# PicoDucky.net
KiCad netlist of a schematic drawn in EasyEDA Pro
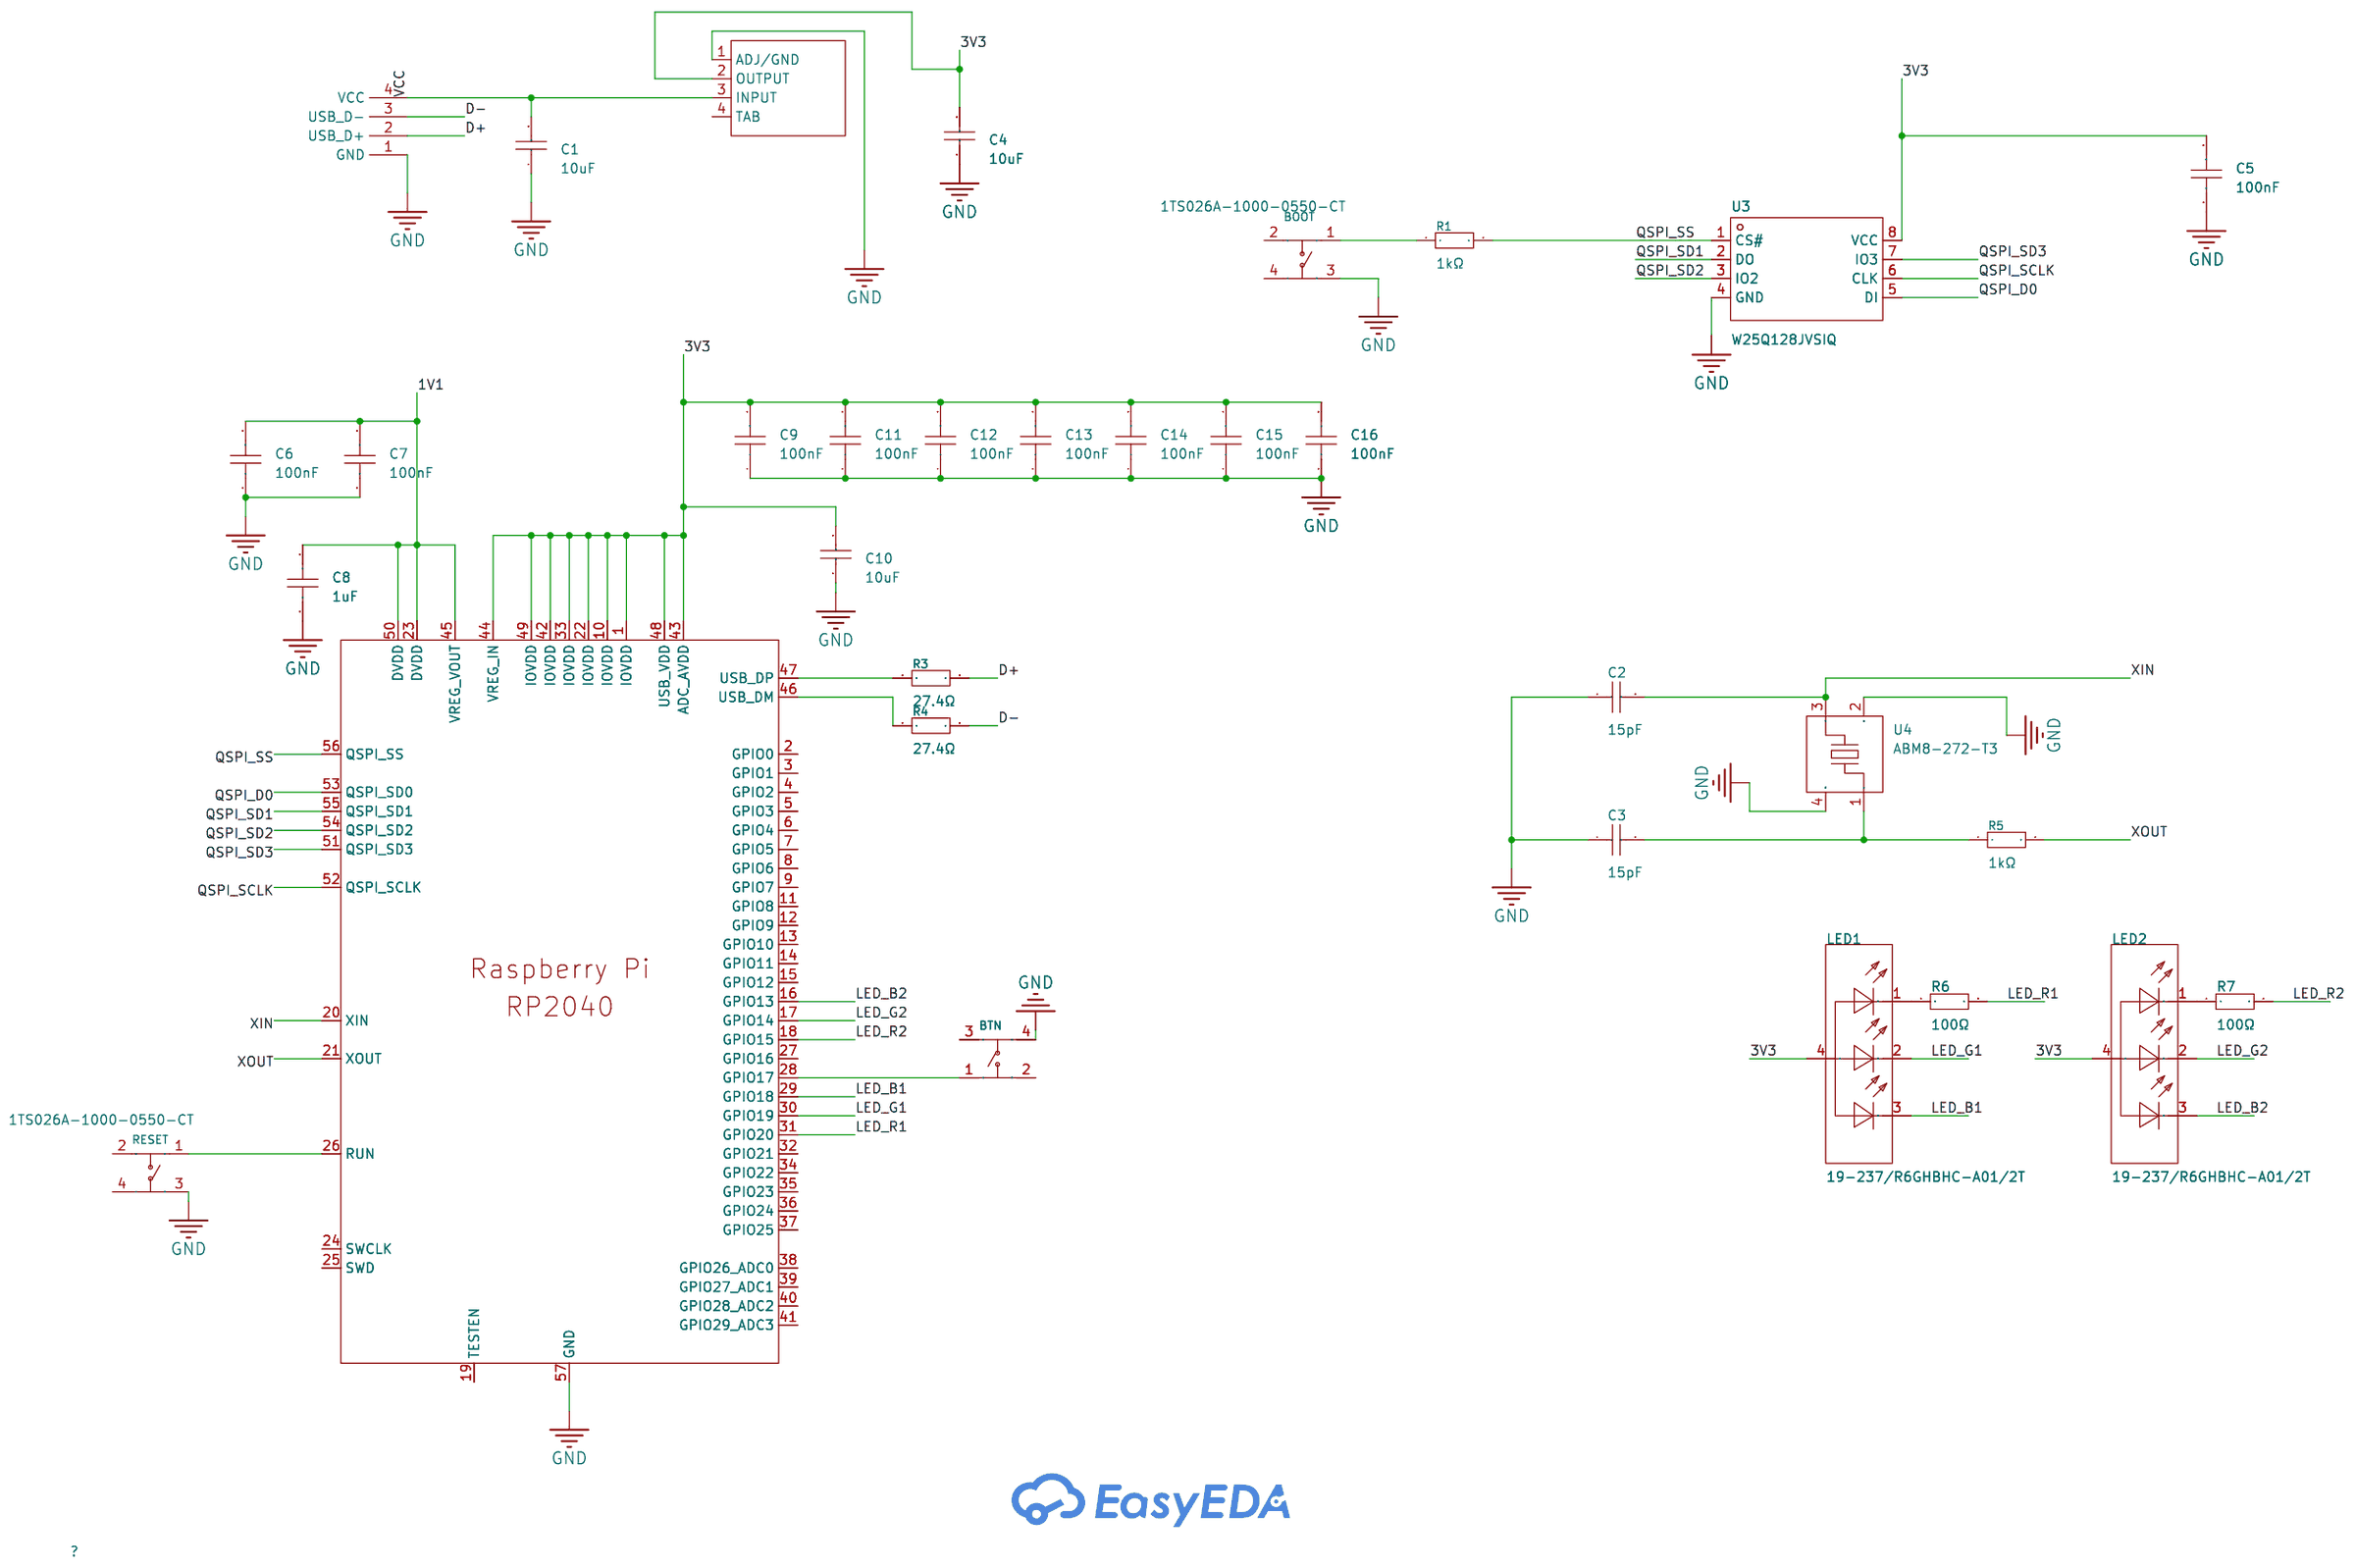
[diagram p0: schematic sheet]

(export (version "E")
  (design (tool "Eeschema 10.0.6"))
  (components
    (comp (ref "BOOT")
      (value "1TS026A-1000-0550-CT")
      (footprint "easyedapro:SW-SMD_4P-L2.6-W1.6-P0.75-LS3.0")
      (fields (field (name "Manufacturer") "HYP(鸿源精密)"))
      (libsource (lib "easyedapro") (part "1TS026A-1000-0550-CT"))
    )
    (comp (ref "BTN")
      (value "1TS026A-1000-0550-CT")
      (footprint "easyedapro:SW-SMD_4P-L2.6-W1.6-P0.75-LS3.0")
      (fields (field (name "Manufacturer") "HYP(鸿源精密)"))
      (libsource (lib "easyedapro") (part "1TS026A-1000-0550-CT"))
    )
    (comp (ref "C1")
      (value "10uF")
      (footprint "easyedapro:C0402")
      (fields
        (field (name "Manufacturer Part") "CL05A106MQ5NUNC")
        (field (name "Manufacturer") "SAMSUNG(三星)")
      )
      (libsource (lib "easyedapro") (part "CL05A106MQ5NUNC"))
    )
    (comp (ref "C2")
      (value "15pF")
      (footprint "easyedapro:C0402")
      (fields (field (name "Manufacturer Part") "0402CG150J500NT") (field (name "Manufacturer") "FH(风华)"))
      (libsource (lib "easyedapro") (part "0402CG150J500NT"))
    )
    (comp (ref "C3")
      (value "15pF")
      (footprint "easyedapro:C0402")
      (fields (field (name "Manufacturer Part") "0402CG150J500NT") (field (name "Manufacturer") "FH(风华)"))
      (libsource (lib "easyedapro") (part "0402CG150J500NT"))
    )
    (comp (ref "C4")
      (value "10uF")
      (footprint "easyedapro:C0402")
      (fields
        (field (name "Manufacturer Part") "CL05A106MQ5NUNC")
        (field (name "Manufacturer") "SAMSUNG(三星)")
      )
      (libsource (lib "easyedapro") (part "CL05A106MQ5NUNC"))
    )
    (comp (ref "C5")
      (value "100nF")
      (footprint "easyedapro:C0402")
      (fields
        (field (name "Manufacturer Part") "CL05B104KO5NNNC")
        (field (name "Manufacturer") "SAMSUNG(三星)")
      )
      (libsource (lib "easyedapro") (part "CL05B104KO5NNNC"))
    )
    (comp (ref "C6")
      (value "100nF")
      (footprint "easyedapro:C0402")
      (fields
        (field (name "Manufacturer Part") "CL05B104KO5NNNC")
        (field (name "Manufacturer") "SAMSUNG(三星)")
      )
      (libsource (lib "easyedapro") (part "CL05B104KO5NNNC"))
    )
    (comp (ref "C7")
      (value "100nF")
      (footprint "easyedapro:C0402")
      (fields
        (field (name "Manufacturer Part") "CL05B104KO5NNNC")
        (field (name "Manufacturer") "SAMSUNG(三星)")
      )
      (libsource (lib "easyedapro") (part "CL05B104KO5NNNC"))
    )
    (comp (ref "C8")
      (value "1uF")
      (footprint "easyedapro:C0402")
      (fields
        (field (name "Manufacturer Part") "CL05A105KA5NQNC")
        (field (name "Manufacturer") "SAMSUNG(三星)")
      )
      (libsource (lib "easyedapro") (part "CL05A105KA5NQNC"))
    )
    (comp (ref "C9")
      (value "100nF")
      (footprint "easyedapro:C0402")
      (fields
        (field (name "Manufacturer Part") "CL05B104KO5NNNC")
        (field (name "Manufacturer") "SAMSUNG(三星)")
      )
      (libsource (lib "easyedapro") (part "CL05B104KO5NNNC"))
    )
    (comp (ref "C10")
      (value "10uF")
      (footprint "easyedapro:C0402")
      (fields
        (field (name "Manufacturer Part") "CL05A106MQ5NUNC")
        (field (name "Manufacturer") "SAMSUNG(三星)")
      )
      (libsource (lib "easyedapro") (part "CL05A106MQ5NUNC"))
    )
    (comp (ref "C11")
      (value "100nF")
      (footprint "easyedapro:C0402")
      (fields
        (field (name "Manufacturer Part") "CL05B104KO5NNNC")
        (field (name "Manufacturer") "SAMSUNG(三星)")
      )
      (libsource (lib "easyedapro") (part "CL05B104KO5NNNC"))
    )
    (comp (ref "C12")
      (value "100nF")
      (footprint "easyedapro:C0402")
      (fields
        (field (name "Manufacturer Part") "CL05B104KO5NNNC")
        (field (name "Manufacturer") "SAMSUNG(三星)")
      )
      (libsource (lib "easyedapro") (part "CL05B104KO5NNNC"))
    )
    (comp (ref "C13")
      (value "100nF")
      (footprint "easyedapro:C0402")
      (fields
        (field (name "Manufacturer Part") "CL05B104KO5NNNC")
        (field (name "Manufacturer") "SAMSUNG(三星)")
      )
      (libsource (lib "easyedapro") (part "CL05B104KO5NNNC"))
    )
    (comp (ref "C14")
      (value "100nF")
      (footprint "easyedapro:C0402")
      (fields
        (field (name "Manufacturer Part") "CL05B104KO5NNNC")
        (field (name "Manufacturer") "SAMSUNG(三星)")
      )
      (libsource (lib "easyedapro") (part "CL05B104KO5NNNC"))
    )
    (comp (ref "C15")
      (value "100nF")
      (footprint "easyedapro:C0402")
      (fields
        (field (name "Manufacturer Part") "CL05B104KO5NNNC")
        (field (name "Manufacturer") "SAMSUNG(三星)")
      )
      (libsource (lib "easyedapro") (part "CL05B104KO5NNNC"))
    )
    (comp (ref "C16")
      (value "100nF")
      (footprint "easyedapro:C0402")
      (fields
        (field (name "Manufacturer Part") "CL05B104KO5NNNC")
        (field (name "Manufacturer") "SAMSUNG(三星)")
      )
      (libsource (lib "easyedapro") (part "CL05B104KO5NNNC"))
    )
    (comp (ref "LED1")
      (value "19-237/R6GHBHC-A01/2T")
      (footprint "easyedapro:LED-ARRAY-SMD_4P-L1.6-W1.6-BL-CW")
      (fields (field (name "Manufacturer") "EVERLIGHT(亿光)"))
      (libsource (lib "easyedapro") (part "19-237/R6GHBHC-A01/2T"))
    )
    (comp (ref "LED2")
      (value "19-237/R6GHBHC-A01/2T")
      (footprint "easyedapro:LED-ARRAY-SMD_4P-L1.6-W1.6-BL-CW")
      (fields (field (name "Manufacturer") "EVERLIGHT(亿光)"))
      (libsource (lib "easyedapro") (part "19-237/R6GHBHC-A01/2T"))
    )
    (comp (ref "R1")
      (value "1kΩ")
      (footprint "easyedapro:R0402")
      (fields
        (field (name "Manufacturer Part") "0402WGF1001TCE")
        (field (name "Manufacturer") "UNI-ROYAL(厚声)")
      )
      (libsource (lib "easyedapro") (part "0402WGF1001TCE"))
    )
    (comp (ref "R3")
      (value "27.4Ω")
      (footprint "easyedapro:R0402")
      (fields
        (field (name "Manufacturer Part") "0402WGF274JTCE")
        (field (name "Manufacturer") "UNI-ROYAL(厚声)")
      )
      (libsource (lib "easyedapro") (part "0402WGF274JTCE"))
    )
    (comp (ref "R4")
      (value "27.4Ω")
      (footprint "easyedapro:R0402")
      (fields
        (field (name "Manufacturer Part") "0402WGF274JTCE")
        (field (name "Manufacturer") "UNI-ROYAL(厚声)")
      )
      (libsource (lib "easyedapro") (part "0402WGF274JTCE"))
    )
    (comp (ref "R5")
      (value "1kΩ")
      (footprint "easyedapro:R0402")
      (fields
        (field (name "Manufacturer Part") "0402WGF1001TCE")
        (field (name "Manufacturer") "UNI-ROYAL(厚声)")
      )
      (libsource (lib "easyedapro") (part "0402WGF1001TCE"))
    )
    (comp (ref "R6")
      (value "100Ω")
      (footprint "easyedapro:R0402")
      (fields
        (field (name "Manufacturer Part") "0402WGF1000TCE")
        (field (name "Manufacturer") "UNI-ROYAL(厚声)")
      )
      (libsource (lib "easyedapro") (part "0402WGF1000TCE"))
    )
    (comp (ref "R7")
      (value "100Ω")
      (footprint "easyedapro:R0402")
      (fields
        (field (name "Manufacturer Part") "0402WGF1000TCE")
        (field (name "Manufacturer") "UNI-ROYAL(厚声)")
      )
      (libsource (lib "easyedapro") (part "0402WGF1000TCE"))
    )
    (comp (ref "RESET")
      (value "1TS026A-1000-0550-CT")
      (footprint "easyedapro:SW-SMD_4P-L2.6-W1.6-P0.75-LS3.0")
      (fields (field (name "Manufacturer") "HYP(鸿源精密)"))
      (libsource (lib "easyedapro") (part "1TS026A-1000-0550-CT"))
    )
    (comp (ref "U1")
      (value "RP2040")
      (footprint "easyedapro:QFN-56_L7.0-W7.0-P0.40-TL-EP4.0")
      (fields (field (name "Manufacturer") "Raspberry Pi(树莓派)"))
      (libsource (lib "easyedapro") (part "RP2040_C2961140"))
    )
    (comp (ref "U2")
      (value "NCP1117ST33T3G")
      (footprint "easyedapro:SOT-223-3_L6.5-W3.4-P2.30-LS7.0-BR")
      (fields (field (name "Manufacturer") "onsemi(安森美)"))
      (libsource (lib "easyedapro") (part "NCP1117ST33T3G"))
    )
    (comp (ref "U3")
      (value "W25Q128JVSIQ")
      (footprint "easyedapro:SOIC-8_L5.3-W5.3-P1.27-LS8.0-BL")
      (fields (field (name "Manufacturer") "WINBOND(华邦)"))
      (libsource (lib "easyedapro") (part "W25Q128JVSIQTR"))
    )
    (comp (ref "U4")
      (value "ABM8-272-T3")
      (footprint "easyedapro:CRYSTAL-SMD_4P-L3.2-W2.5-BL")
      (fields (field (name "Manufacturer") "ABRACON"))
      (libsource (lib "easyedapro") (part "ABM8-272-T3_C20625731"))
    )
    (comp (ref "X1")
      (value "~")
      (footprint "easyedapro:USBA_PCB")
      (description "USB-A PCB")
      (libsource (lib "easyedapro") (part "USBA_PCB"))
    )
  )
  (nets
    (net (code "1") (name "/1V1") (class "Default")
      (node (ref "C6") (pin "2") (pinfunction "2_2") (pintype "unspecified"))
      (node (ref "C7") (pin "2") (pinfunction "2_2") (pintype "unspecified"))
      (node (ref "C8") (pin "2") (pinfunction "2_2") (pintype "unspecified"))
      (node (ref "U1") (pin "23") (pinfunction "DVDD_23") (pintype "bidirectional"))
      (node (ref "U1") (pin "45") (pinfunction "VREG_VOUT_45") (pintype "bidirectional"))
      (node (ref "U1") (pin "50") (pinfunction "DVDD_50") (pintype "bidirectional"))
    )
    (net (code "2") (name "/3V3") (class "Default")
      (node (ref "C10") (pin "2") (pinfunction "2_2") (pintype "input"))
      (node (ref "C11") (pin "2") (pinfunction "2_2") (pintype "unspecified"))
      (node (ref "C12") (pin "2") (pinfunction "2_2") (pintype "unspecified"))
      (node (ref "C13") (pin "2") (pinfunction "2_2") (pintype "unspecified"))
      (node (ref "C14") (pin "2") (pinfunction "2_2") (pintype "unspecified"))
      (node (ref "C15") (pin "2") (pinfunction "2_2") (pintype "unspecified"))
      (node (ref "C16") (pin "2") (pinfunction "2_2") (pintype "unspecified"))
      (node (ref "C4") (pin "2") (pinfunction "2_2") (pintype "input"))
      (node (ref "C5") (pin "2") (pinfunction "2_2") (pintype "unspecified"))
      (node (ref "C9") (pin "2") (pinfunction "2_2") (pintype "unspecified"))
      (node (ref "LED1") (pin "4") (pinfunction "+_4") (pintype "unspecified"))
      (node (ref "LED2") (pin "4") (pinfunction "+_4") (pintype "unspecified"))
      (node (ref "U1") (pin "1") (pinfunction "IOVDD_1") (pintype "bidirectional"))
      (node (ref "U1") (pin "10") (pinfunction "IOVDD_10") (pintype "bidirectional"))
      (node (ref "U1") (pin "22") (pinfunction "IOVDD_22") (pintype "bidirectional"))
      (node (ref "U1") (pin "33") (pinfunction "IOVDD_33") (pintype "bidirectional"))
      (node (ref "U1") (pin "42") (pinfunction "IOVDD_42") (pintype "bidirectional"))
      (node (ref "U1") (pin "43") (pinfunction "ADC_AVDD_43") (pintype "bidirectional"))
      (node (ref "U1") (pin "44") (pinfunction "VREG_IN_44") (pintype "bidirectional"))
      (node (ref "U1") (pin "48") (pinfunction "USB_VDD_48") (pintype "bidirectional"))
      (node (ref "U1") (pin "49") (pinfunction "IOVDD_49") (pintype "bidirectional"))
      (node (ref "U2") (pin "2") (pinfunction "OUTPUT_2") (pintype "unspecified"))
      (node (ref "U3") (pin "8") (pinfunction "VCC_8") (pintype "unspecified"))
    )
    (net (code "3") (name "/D+") (class "Default")
      (node (ref "R3") (pin "2") (pinfunction "2_2") (pintype "input"))
      (node (ref "X1") (pin "2") (pinfunction "USB_D+_2") (pintype "input"))
    )
    (net (code "4") (name "/D-") (class "Default")
      (node (ref "R4") (pin "2") (pinfunction "2_2") (pintype "input"))
      (node (ref "X1") (pin "3") (pinfunction "USB_D-_3") (pintype "input"))
    )
    (net (code "5") (name "/LED_B1") (class "Default")
      (node (ref "LED1") (pin "3") (pinfunction "B-_3") (pintype "unspecified"))
      (node (ref "U1") (pin "29") (pinfunction "GPIO18_29") (pintype "bidirectional"))
    )
    (net (code "6") (name "/LED_B2") (class "Default")
      (node (ref "LED2") (pin "3") (pinfunction "B-_3") (pintype "unspecified"))
      (node (ref "U1") (pin "16") (pinfunction "GPIO13_16") (pintype "bidirectional"))
    )
    (net (code "7") (name "/LED_G1") (class "Default")
      (node (ref "LED1") (pin "2") (pinfunction "G-_2") (pintype "unspecified"))
      (node (ref "U1") (pin "30") (pinfunction "GPIO19_30") (pintype "bidirectional"))
    )
    (net (code "8") (name "/LED_G2") (class "Default")
      (node (ref "LED2") (pin "2") (pinfunction "G-_2") (pintype "unspecified"))
      (node (ref "U1") (pin "17") (pinfunction "GPIO14_17") (pintype "bidirectional"))
    )
    (net (code "9") (name "/LED_R1") (class "Default")
      (node (ref "R6") (pin "2") (pinfunction "2_2") (pintype "input"))
      (node (ref "U1") (pin "31") (pinfunction "GPIO20_31") (pintype "bidirectional"))
    )
    (net (code "10") (name "/LED_R2") (class "Default")
      (node (ref "R7") (pin "2") (pinfunction "2_2") (pintype "input"))
      (node (ref "U1") (pin "18") (pinfunction "GPIO15_18") (pintype "bidirectional"))
    )
    (net (code "11") (name "/QSPI_D0") (class "Default")
      (node (ref "U1") (pin "53") (pinfunction "QSPI_SD0_53") (pintype "bidirectional"))
      (node (ref "U3") (pin "5") (pinfunction "DI_5") (pintype "unspecified"))
    )
    (net (code "12") (name "/QSPI_SCLK") (class "Default")
      (node (ref "U1") (pin "52") (pinfunction "QSPI_SCLK_52") (pintype "output"))
      (node (ref "U3") (pin "6") (pinfunction "CLK_6") (pintype "unspecified"))
    )
    (net (code "13") (name "/QSPI_SD1") (class "Default")
      (node (ref "U1") (pin "55") (pinfunction "QSPI_SD1_55") (pintype "bidirectional"))
      (node (ref "U3") (pin "2") (pinfunction "DO_2") (pintype "unspecified"))
    )
    (net (code "14") (name "/QSPI_SD2") (class "Default")
      (node (ref "U1") (pin "54") (pinfunction "QSPI_SD2_54") (pintype "bidirectional"))
      (node (ref "U3") (pin "3") (pinfunction "IO2_3") (pintype "unspecified"))
    )
    (net (code "15") (name "/QSPI_SD3") (class "Default")
      (node (ref "U1") (pin "51") (pinfunction "QSPI_SD3_51") (pintype "bidirectional"))
      (node (ref "U3") (pin "7") (pinfunction "IO3_7") (pintype "unspecified"))
    )
    (net (code "16") (name "/QSPI_SS") (class "Default")
      (node (ref "R1") (pin "2") (pinfunction "2_2") (pintype "input"))
      (node (ref "U1") (pin "56") (pinfunction "QSPI_SS_56") (pintype "bidirectional"))
      (node (ref "U3") (pin "1") (pinfunction "CS#_1") (pintype "unspecified"))
    )
    (net (code "17") (name "/VCC") (class "Default")
      (node (ref "C1") (pin "2") (pinfunction "2_2") (pintype "input"))
      (node (ref "U2") (pin "3") (pinfunction "INPUT_3") (pintype "unspecified"))
      (node (ref "X1") (pin "4") (pinfunction "VCC_4") (pintype "input"))
    )
    (net (code "18") (name "/XIN") (class "Default")
      (node (ref "C2") (pin "2") (pinfunction "2_2") (pintype "input"))
      (node (ref "U1") (pin "20") (pinfunction "XIN_20") (pintype "input"))
      (node (ref "U4") (pin "3") (pinfunction "3_3") (pintype "input"))
    )
    (net (code "19") (name "/XOUT") (class "Default")
      (node (ref "R5") (pin "2") (pinfunction "2_2") (pintype "input"))
      (node (ref "U1") (pin "21") (pinfunction "XOUT_21") (pintype "unspecified"))
    )
    (net (code "20") (name "GND") (class "Default")
      (node (ref "BOOT") (pin "3") (pinfunction "3_3") (pintype "input"))
      (node (ref "BTN") (pin "4") (pinfunction "4_4") (pintype "input"))
      (node (ref "C1") (pin "1") (pinfunction "1_1") (pintype "input"))
      (node (ref "C10") (pin "1") (pinfunction "1_1") (pintype "input"))
      (node (ref "C11") (pin "1") (pinfunction "1_1") (pintype "unspecified"))
      (node (ref "C12") (pin "1") (pinfunction "1_1") (pintype "unspecified"))
      (node (ref "C13") (pin "1") (pinfunction "1_1") (pintype "unspecified"))
      (node (ref "C14") (pin "1") (pinfunction "1_1") (pintype "unspecified"))
      (node (ref "C15") (pin "1") (pinfunction "1_1") (pintype "unspecified"))
      (node (ref "C16") (pin "1") (pinfunction "1_1") (pintype "unspecified"))
      (node (ref "C2") (pin "1") (pinfunction "1_1") (pintype "input"))
      (node (ref "C3") (pin "1") (pinfunction "1_1") (pintype "input"))
      (node (ref "C4") (pin "1") (pinfunction "1_1") (pintype "input"))
      (node (ref "C5") (pin "1") (pinfunction "1_1") (pintype "unspecified"))
      (node (ref "C6") (pin "1") (pinfunction "1_1") (pintype "unspecified"))
      (node (ref "C7") (pin "1") (pinfunction "1_1") (pintype "unspecified"))
      (node (ref "C8") (pin "1") (pinfunction "1_1") (pintype "unspecified"))
      (node (ref "C9") (pin "1") (pinfunction "1_1") (pintype "unspecified"))
      (node (ref "RESET") (pin "3") (pinfunction "3_3") (pintype "input"))
      (node (ref "U1") (pin "57") (pinfunction "GND_57") (pintype "bidirectional"))
      (node (ref "U2") (pin "1") (pinfunction "ADJ/GND_1") (pintype "unspecified"))
      (node (ref "U3") (pin "4") (pinfunction "GND_4") (pintype "unspecified"))
      (node (ref "U4") (pin "2") (pinfunction "GND_2") (pintype "input"))
      (node (ref "U4") (pin "4") (pinfunction "GND_4") (pintype "input"))
      (node (ref "X1") (pin "1") (pinfunction "GND_1") (pintype "input"))
    )
    (net (code "21") (name "Net-(BOOT-Pad1)") (class "Default")
      (node (ref "BOOT") (pin "1") (pinfunction "1_1") (pintype "input"))
      (node (ref "R1") (pin "1") (pinfunction "1_1") (pintype "input"))
    )
    (net (code "22") (name "Net-(C3-Pad2)") (class "Default")
      (node (ref "C3") (pin "2") (pinfunction "2_2") (pintype "input"))
      (node (ref "R5") (pin "1") (pinfunction "1_1") (pintype "input"))
      (node (ref "U4") (pin "1") (pinfunction "1_1") (pintype "input"))
    )
    (net (code "23") (name "Net-(LED1-R-)") (class "Default")
      (node (ref "LED1") (pin "1") (pinfunction "R-_1") (pintype "unspecified"))
      (node (ref "R6") (pin "1") (pinfunction "1_1") (pintype "input"))
    )
    (net (code "24") (name "Net-(LED2-R-)") (class "Default")
      (node (ref "LED2") (pin "1") (pinfunction "R-_1") (pintype "unspecified"))
      (node (ref "R7") (pin "1") (pinfunction "1_1") (pintype "input"))
    )
    (net (code "25") (name "Net-(U1-GPIO17)") (class "Default")
      (node (ref "BTN") (pin "1") (pinfunction "1_1") (pintype "input"))
      (node (ref "U1") (pin "28") (pinfunction "GPIO17_28") (pintype "bidirectional"))
    )
    (net (code "26") (name "Net-(U1-RUN)") (class "Default")
      (node (ref "RESET") (pin "1") (pinfunction "1_1") (pintype "input"))
      (node (ref "U1") (pin "26") (pinfunction "RUN_26") (pintype "input"))
    )
    (net (code "27") (name "Net-(U1-USB_DM)") (class "Default")
      (node (ref "R4") (pin "1") (pinfunction "1_1") (pintype "input"))
      (node (ref "U1") (pin "46") (pinfunction "USB_DM_46") (pintype "bidirectional"))
    )
    (net (code "28") (name "Net-(U1-USB_DP)") (class "Default")
      (node (ref "R3") (pin "1") (pinfunction "1_1") (pintype "input"))
      (node (ref "U1") (pin "47") (pinfunction "USB_DP_47") (pintype "bidirectional"))
    )
    (net (code "29") (name "unconnected-(BOOT-Pad2)") (class "Default")
      (node (ref "BOOT") (pin "2") (pinfunction "2_2") (pintype "input"))
    )
    (net (code "30") (name "unconnected-(BOOT-Pad4)") (class "Default")
      (node (ref "BOOT") (pin "4") (pinfunction "4_4") (pintype "input"))
    )
    (net (code "31") (name "unconnected-(BTN-Pad2)") (class "Default")
      (node (ref "BTN") (pin "2") (pinfunction "2_2") (pintype "input"))
    )
    (net (code "32") (name "unconnected-(BTN-Pad3)") (class "Default")
      (node (ref "BTN") (pin "3") (pinfunction "3_3") (pintype "input"))
    )
    (net (code "33") (name "unconnected-(RESET-Pad2)") (class "Default")
      (node (ref "RESET") (pin "2") (pinfunction "2_2") (pintype "input"))
    )
    (net (code "34") (name "unconnected-(RESET-Pad4)") (class "Default")
      (node (ref "RESET") (pin "4") (pinfunction "4_4") (pintype "input"))
    )
    (net (code "35") (name "unconnected-(U1-GPIO0-Pad2)") (class "Default")
      (node (ref "U1") (pin "2") (pinfunction "GPIO0_2") (pintype "bidirectional"))
    )
    (net (code "36") (name "unconnected-(U1-GPIO1-Pad3)") (class "Default")
      (node (ref "U1") (pin "3") (pinfunction "GPIO1_3") (pintype "bidirectional"))
    )
    (net (code "37") (name "unconnected-(U1-GPIO2-Pad4)") (class "Default")
      (node (ref "U1") (pin "4") (pinfunction "GPIO2_4") (pintype "bidirectional"))
    )
    (net (code "38") (name "unconnected-(U1-GPIO3-Pad5)") (class "Default")
      (node (ref "U1") (pin "5") (pinfunction "GPIO3_5") (pintype "bidirectional"))
    )
    (net (code "39") (name "unconnected-(U1-GPIO4-Pad6)") (class "Default")
      (node (ref "U1") (pin "6") (pinfunction "GPIO4_6") (pintype "bidirectional"))
    )
    (net (code "40") (name "unconnected-(U1-GPIO5-Pad7)") (class "Default")
      (node (ref "U1") (pin "7") (pinfunction "GPIO5_7") (pintype "bidirectional"))
    )
    (net (code "41") (name "unconnected-(U1-GPIO6-Pad8)") (class "Default")
      (node (ref "U1") (pin "8") (pinfunction "GPIO6_8") (pintype "bidirectional"))
    )
    (net (code "42") (name "unconnected-(U1-GPIO7-Pad9)") (class "Default")
      (node (ref "U1") (pin "9") (pinfunction "GPIO7_9") (pintype "bidirectional"))
    )
    (net (code "43") (name "unconnected-(U1-GPIO8-Pad11)") (class "Default")
      (node (ref "U1") (pin "11") (pinfunction "GPIO8_11") (pintype "bidirectional"))
    )
    (net (code "44") (name "unconnected-(U1-GPIO9-Pad12)") (class "Default")
      (node (ref "U1") (pin "12") (pinfunction "GPIO9_12") (pintype "bidirectional"))
    )
    (net (code "45") (name "unconnected-(U1-GPIO10-Pad13)") (class "Default")
      (node (ref "U1") (pin "13") (pinfunction "GPIO10_13") (pintype "bidirectional"))
    )
    (net (code "46") (name "unconnected-(U1-GPIO11-Pad14)") (class "Default")
      (node (ref "U1") (pin "14") (pinfunction "GPIO11_14") (pintype "bidirectional"))
    )
    (net (code "47") (name "unconnected-(U1-GPIO12-Pad15)") (class "Default")
      (node (ref "U1") (pin "15") (pinfunction "GPIO12_15") (pintype "bidirectional"))
    )
    (net (code "48") (name "unconnected-(U1-GPIO16-Pad27)") (class "Default")
      (node (ref "U1") (pin "27") (pinfunction "GPIO16_27") (pintype "bidirectional"))
    )
    (net (code "49") (name "unconnected-(U1-GPIO21-Pad32)") (class "Default")
      (node (ref "U1") (pin "32") (pinfunction "GPIO21_32") (pintype "bidirectional"))
    )
    (net (code "50") (name "unconnected-(U1-GPIO22-Pad34)") (class "Default")
      (node (ref "U1") (pin "34") (pinfunction "GPIO22_34") (pintype "bidirectional"))
    )
    (net (code "51") (name "unconnected-(U1-GPIO23-Pad35)") (class "Default")
      (node (ref "U1") (pin "35") (pinfunction "GPIO23_35") (pintype "bidirectional"))
    )
    (net (code "52") (name "unconnected-(U1-GPIO24-Pad36)") (class "Default")
      (node (ref "U1") (pin "36") (pinfunction "GPIO24_36") (pintype "bidirectional"))
    )
    (net (code "53") (name "unconnected-(U1-GPIO25-Pad37)") (class "Default")
      (node (ref "U1") (pin "37") (pinfunction "GPIO25_37") (pintype "bidirectional"))
    )
    (net (code "54") (name "unconnected-(U1-GPIO26_ADC0-Pad38)") (class "Default")
      (node (ref "U1") (pin "38") (pinfunction "GPIO26_ADC0_38") (pintype "bidirectional"))
    )
    (net (code "55") (name "unconnected-(U1-GPIO27_ADC1-Pad39)") (class "Default")
      (node (ref "U1") (pin "39") (pinfunction "GPIO27_ADC1_39") (pintype "bidirectional"))
    )
    (net (code "56") (name "unconnected-(U1-GPIO28_ADC2-Pad40)") (class "Default")
      (node (ref "U1") (pin "40") (pinfunction "GPIO28_ADC2_40") (pintype "bidirectional"))
    )
    (net (code "57") (name "unconnected-(U1-GPIO29_ADC3-Pad41)") (class "Default")
      (node (ref "U1") (pin "41") (pinfunction "GPIO29_ADC3_41") (pintype "bidirectional"))
    )
    (net (code "58") (name "unconnected-(U1-SWCLK-Pad24)") (class "Default")
      (node (ref "U1") (pin "24") (pinfunction "SWCLK_24") (pintype "output"))
    )
    (net (code "59") (name "unconnected-(U1-SWD-Pad25)") (class "Default")
      (node (ref "U1") (pin "25") (pinfunction "SWD_25") (pintype "bidirectional"))
    )
    (net (code "60") (name "unconnected-(U1-TESTEN-Pad19)") (class "Default")
      (node (ref "U1") (pin "19") (pinfunction "TESTEN_19") (pintype "unspecified"))
    )
    (net (code "61") (name "unconnected-(U2-TAB-Pad4)") (class "Default")
      (node (ref "U2") (pin "4") (pinfunction "TAB_4") (pintype "unspecified"))
    )
  )
)
